# ClockUSB.net
KiCad netlist of a schematic drawn in EAGLE
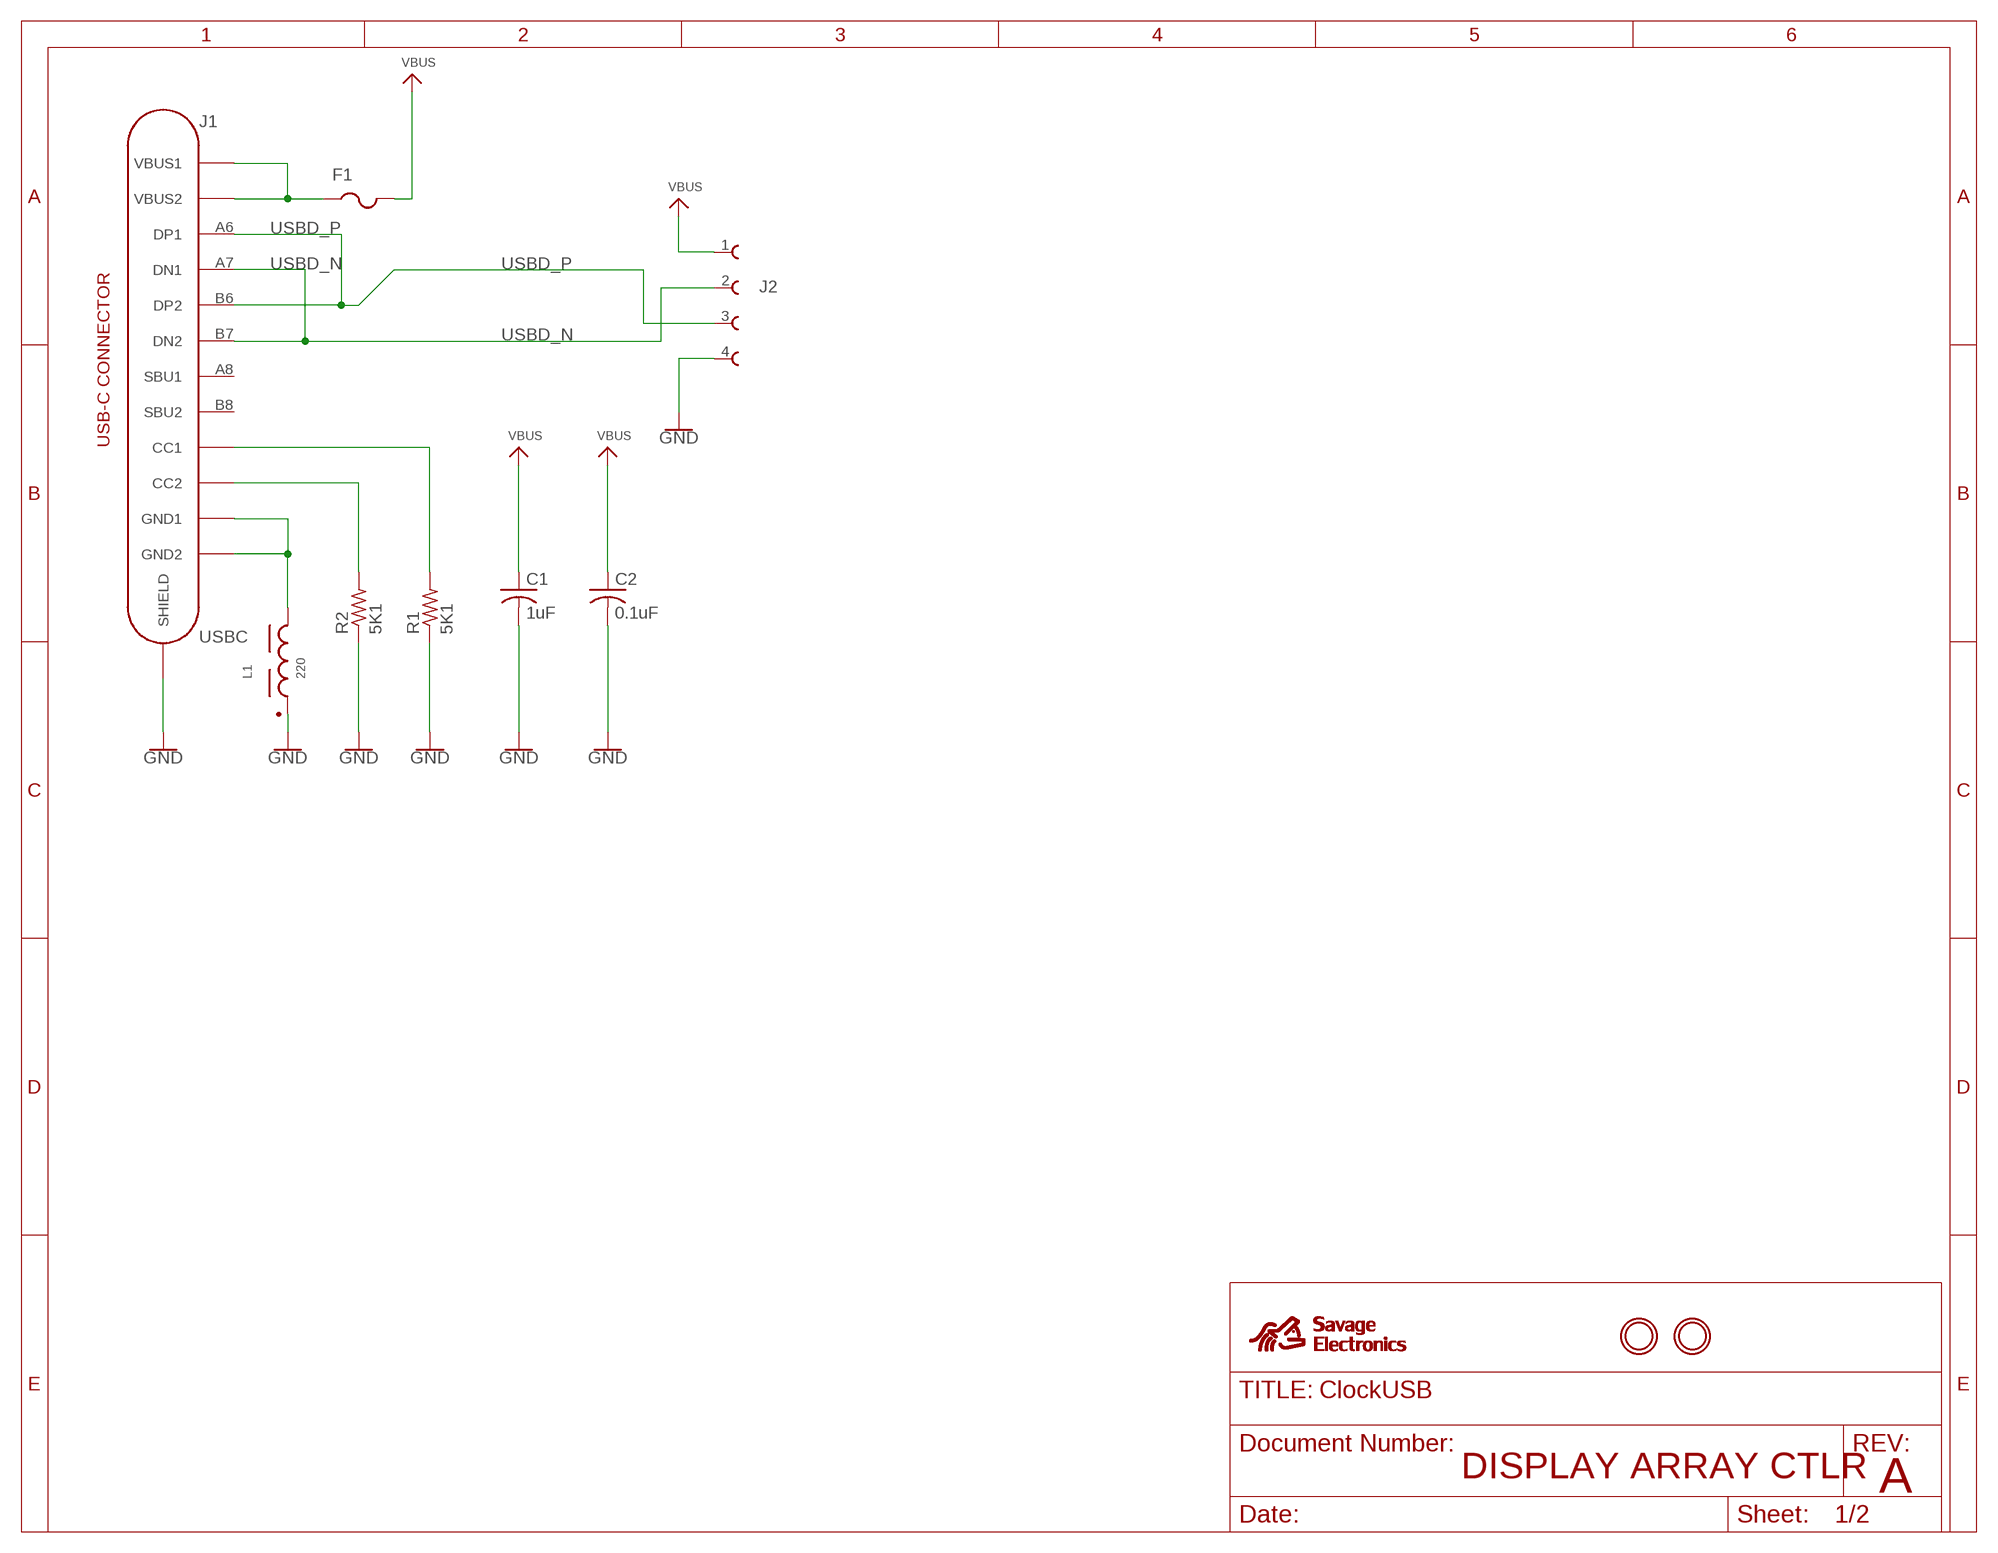
[diagram p0: schematic, sheet 1]
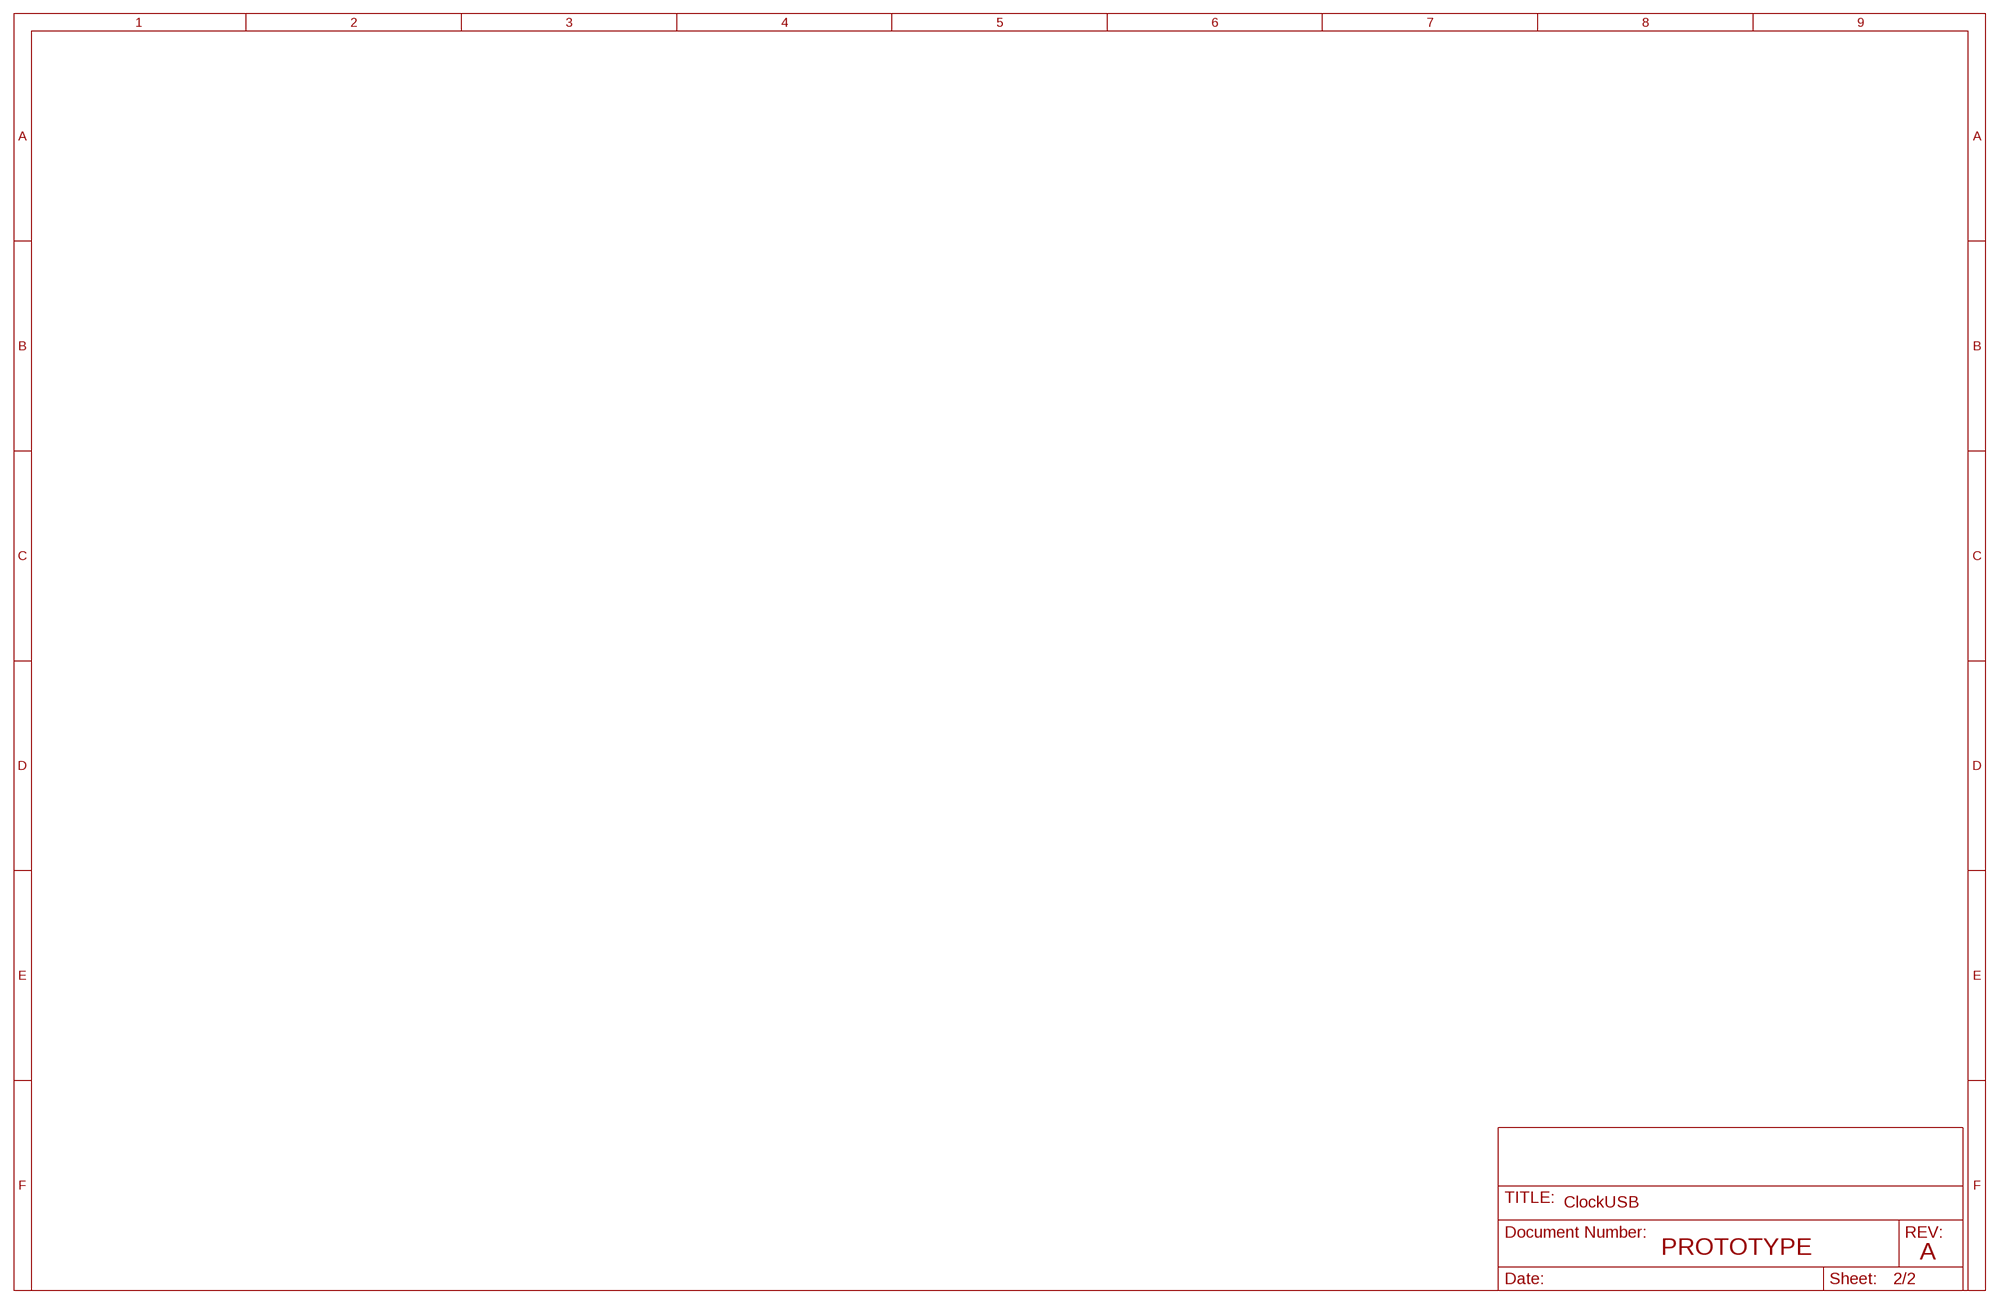
[diagram p1: schematic, sheet 2]

(export (version "E")
  (design (tool "Eeschema 10.0.6"))
  (components
    (comp (ref "C1")
      (value "1uF")
      (footprint "eagle-import:C0603")
      (libsource (lib "eagle-import") (part "C-USC0603"))
    )
    (comp (ref "C2")
      (value "0.1uF")
      (footprint "eagle-import:C0603")
      (libsource (lib "eagle-import") (part "C-USC0603"))
    )
    (comp (ref "F1")
      (value "PTCFUSE")
      (footprint "eagle-import:R0603")
      (libsource (lib "eagle-import") (part "PTCFUSE"))
    )
    (comp (ref "J1")
      (value "USBC")
      (footprint "eagle-import:USBC")
      (libsource (lib "eagle-import") (part "USBC"))
    )
    (comp (ref "J2")
      (value "62000411121")
      (footprint "eagle-import:62000411121")
      (libsource (lib "eagle-import") (part "62000411121"))
    )
    (comp (ref "L1")
      (value "220")
      (footprint "eagle-import:WE-CBA_0603(W=2.2)")
      (libsource (lib "eagle-import") (part "WE-CBA_0603_WB/HS_782631182"))
    )
    (comp (ref "R1")
      (value "5K1")
      (footprint "eagle-import:R0603")
      (libsource (lib "eagle-import") (part "R-US_R0603"))
    )
    (comp (ref "R2")
      (value "5K1")
      (footprint "eagle-import:R0603")
      (libsource (lib "eagle-import") (part "R-US_R0603"))
    )
    (comp (ref "U$3")
      (value "SE_SMALL_FSILK")
      (footprint "eagle-import:SE_SMALL_FACESILK")
      (libsource (lib "eagle-import") (part "SE_SMALL_FSILK"))
    )
    (comp (ref "U$6")
      (value "MOUNTINGHOLE3.0THIN")
      (footprint "eagle-import:MOUNTINGHOLE_3.0_PLATEDTHIN")
      (libsource (lib "eagle-import") (part "MOUNTINGHOLE3.0THIN"))
    )
    (comp (ref "U$7")
      (value "MOUNTINGHOLE3.0THIN")
      (footprint "eagle-import:MOUNTINGHOLE_3.0_PLATEDTHIN")
      (libsource (lib "eagle-import") (part "MOUNTINGHOLE3.0THIN"))
    )
  )
  (nets
    (net (code "1") (name "GND") (class "Default")
      (node (ref "C1") (pin "2") (pinfunction "2_2") (pintype "passive"))
      (node (ref "C2") (pin "2") (pinfunction "2_2") (pintype "passive"))
      (node (ref "J1") (pin "S1") (pinfunction "SHIELD_S1") (pintype "bidirectional"))
      (node (ref "J1") (pin "S2") (pinfunction "SHIELD_S2") (pintype "bidirectional"))
      (node (ref "J1") (pin "S3") (pinfunction "SHIELD_S3") (pintype "bidirectional"))
      (node (ref "J1") (pin "S4") (pinfunction "SHIELD_S4") (pintype "bidirectional"))
      (node (ref "J2") (pin "4") (pinfunction "4_4") (pintype "passive"))
      (node (ref "L1") (pin "1") (pinfunction "1_1") (pintype "passive"))
      (node (ref "R1") (pin "1") (pinfunction "1_1") (pintype "passive"))
      (node (ref "R2") (pin "1") (pinfunction "1_1") (pintype "passive"))
    )
    (net (code "2") (name "Net-(J1-CC1)") (class "Default")
      (node (ref "J1") (pin "A5") (pinfunction "CC1_A5") (pintype "bidirectional"))
      (node (ref "R1") (pin "2") (pinfunction "2_2") (pintype "passive"))
    )
    (net (code "3") (name "Net-(J1-CC2)") (class "Default")
      (node (ref "J1") (pin "B5") (pinfunction "CC2_B5") (pintype "bidirectional"))
      (node (ref "R2") (pin "2") (pinfunction "2_2") (pintype "passive"))
    )
    (net (code "4") (name "Net-(J1-GND1)") (class "Default")
      (node (ref "J1") (pin "A1B12") (pinfunction "GND1_A1B12") (pintype "bidirectional"))
      (node (ref "J1") (pin "B1A12") (pinfunction "GND2_B1A12") (pintype "bidirectional"))
      (node (ref "L1") (pin "2") (pinfunction "2_2") (pintype "passive"))
    )
    (net (code "5") (name "Net-(J1-VBUS1)") (class "Default")
      (node (ref "F1") (pin "1") (pinfunction "1_1") (pintype "passive"))
      (node (ref "J1") (pin "A4B9") (pinfunction "VBUS1_A4B9") (pintype "bidirectional"))
      (node (ref "J1") (pin "B4A9") (pinfunction "VBUS2_B4A9") (pintype "bidirectional"))
    )
    (net (code "6") (name "USBD_N") (class "Default")
      (node (ref "J1") (pin "A7") (pinfunction "DN1_A7") (pintype "bidirectional"))
      (node (ref "J1") (pin "B7") (pinfunction "DN2_B7") (pintype "bidirectional"))
      (node (ref "J2") (pin "2") (pinfunction "2_2") (pintype "passive"))
    )
    (net (code "7") (name "USBD_P") (class "Default")
      (node (ref "J1") (pin "A6") (pinfunction "DP1_A6") (pintype "bidirectional"))
      (node (ref "J1") (pin "B6") (pinfunction "DP2_B6") (pintype "bidirectional"))
      (node (ref "J2") (pin "3") (pinfunction "3_3") (pintype "passive"))
    )
    (net (code "8") (name "VBUS") (class "Default")
      (node (ref "C1") (pin "1") (pinfunction "1_1") (pintype "passive"))
      (node (ref "C2") (pin "1") (pinfunction "1_1") (pintype "passive"))
      (node (ref "F1") (pin "2") (pinfunction "2_2") (pintype "passive"))
      (node (ref "J2") (pin "1") (pinfunction "1_1") (pintype "passive"))
    )
    (net (code "9") (name "unconnected-(J1-SBU1-PadA8)") (class "Default")
      (node (ref "J1") (pin "A8") (pinfunction "SBU1_A8") (pintype "bidirectional"))
    )
    (net (code "10") (name "unconnected-(J1-SBU2-PadB8)") (class "Default")
      (node (ref "J1") (pin "B8") (pinfunction "SBU2_B8") (pintype "bidirectional"))
    )
  )
)
